# MainBoardSchematic.net
KiCad netlist of a schematic drawn in Altium Designer
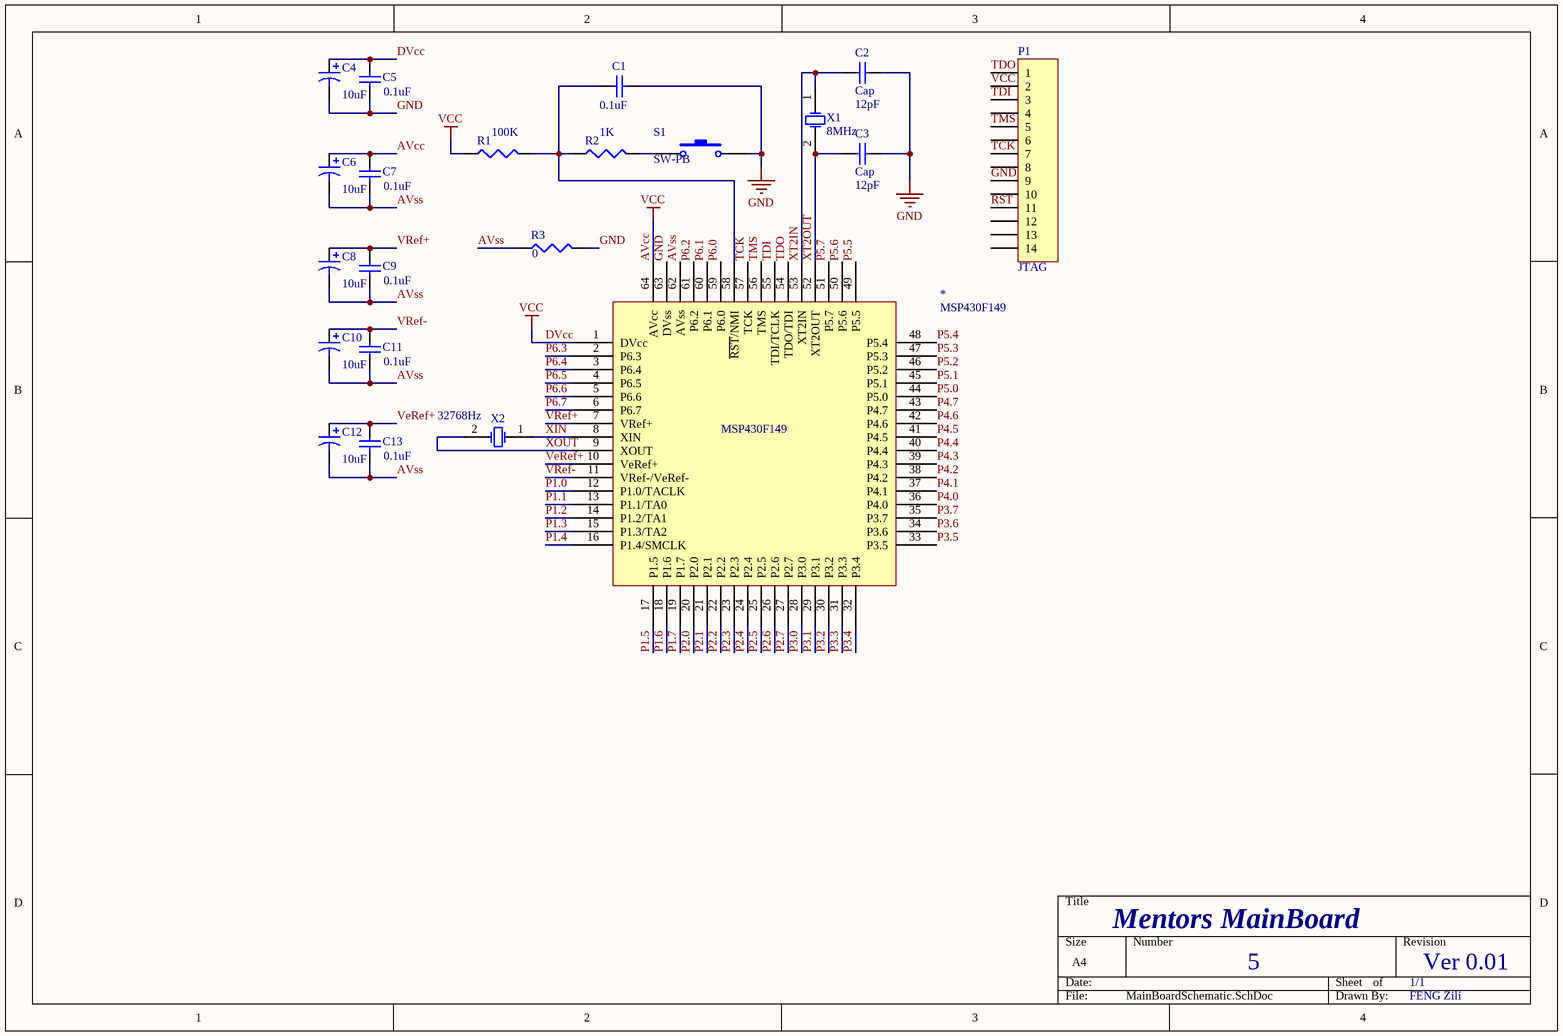
[diagram p0: MainBoardSchematic.SchDoc]

(export (version "E")
  (design (tool "Eeschema 10.0.6"))
  (components
    (comp (ref "*") (value "MSP430F149") (libsource (lib "schMSP430") (part "MSP430F149")))
    (comp (ref "C1")
      (value "0.1uF")
      (footprint "RAD-0.3")
      (description "Capacitor")
      (fields (field (name "Comment") "Cap") (field (name "PUBLISHER") "Altium Limited"))
      (libsource (lib "Miscellaneous Devices") (part "Cap"))
    )
    (comp (ref "C2")
      (value "Cap")
      (footprint "RAD-0.3")
      (description "Capacitor")
      (fields (field (name "ALTIUM_VALUE") "12pF") (field (name "PUBLISHER") "Altium Limited"))
      (libsource (lib "Miscellaneous Devices") (part "Cap"))
    )
    (comp (ref "C3")
      (value "Cap")
      (footprint "RAD-0.3")
      (description "Capacitor")
      (fields (field (name "ALTIUM_VALUE") "12pF") (field (name "PUBLISHER") "Altium Limited"))
      (libsource (lib "Miscellaneous Devices") (part "Cap"))
    )
    (comp (ref "C4")
      (value "10uF")
      (footprint "C0805")
      (description "Polarized Capacitor (Surface Mount)")
      (fields (field (name "Comment") "Cap Pol3") (field (name "PUBLISHER") "Altium Limited"))
      (libsource (lib "Miscellaneous Devices") (part "Cap Pol3"))
    )
    (comp (ref "C5")
      (value "0.1uF")
      (footprint "RAD-0.3")
      (description "Capacitor")
      (fields (field (name "Comment") "Cap") (field (name "PUBLISHER") "Altium Limited"))
      (libsource (lib "Miscellaneous Devices") (part "Cap"))
    )
    (comp (ref "C6")
      (value "10uF")
      (footprint "C0805")
      (description "Polarized Capacitor (Surface Mount)")
      (fields (field (name "Comment") "Cap Pol3") (field (name "PUBLISHER") "Altium Limited"))
      (libsource (lib "Miscellaneous Devices") (part "Cap Pol3"))
    )
    (comp (ref "C7")
      (value "0.1uF")
      (footprint "RAD-0.3")
      (description "Capacitor")
      (fields (field (name "Comment") "Cap") (field (name "PUBLISHER") "Altium Limited"))
      (libsource (lib "Miscellaneous Devices") (part "Cap"))
    )
    (comp (ref "C8")
      (value "10uF")
      (footprint "C0805")
      (description "Polarized Capacitor (Surface Mount)")
      (fields (field (name "Comment") "Cap Pol3") (field (name "PUBLISHER") "Altium Limited"))
      (libsource (lib "Miscellaneous Devices") (part "Cap Pol3"))
    )
    (comp (ref "C9")
      (value "0.1uF")
      (footprint "RAD-0.3")
      (description "Capacitor")
      (fields (field (name "Comment") "Cap") (field (name "PUBLISHER") "Altium Limited"))
      (libsource (lib "Miscellaneous Devices") (part "Cap"))
    )
    (comp (ref "C10")
      (value "10uF")
      (footprint "C0805")
      (description "Polarized Capacitor (Surface Mount)")
      (fields (field (name "Comment") "Cap Pol3") (field (name "PUBLISHER") "Altium Limited"))
      (libsource (lib "Miscellaneous Devices") (part "Cap Pol3"))
    )
    (comp (ref "C11")
      (value "0.1uF")
      (footprint "RAD-0.3")
      (description "Capacitor")
      (fields (field (name "Comment") "Cap") (field (name "PUBLISHER") "Altium Limited"))
      (libsource (lib "Miscellaneous Devices") (part "Cap"))
    )
    (comp (ref "C12")
      (value "10uF")
      (footprint "C0805")
      (description "Polarized Capacitor (Surface Mount)")
      (fields (field (name "Comment") "Cap Pol3") (field (name "PUBLISHER") "Altium Limited"))
      (libsource (lib "Miscellaneous Devices") (part "Cap Pol3"))
    )
    (comp (ref "C13")
      (value "0.1uF")
      (footprint "RAD-0.3")
      (description "Capacitor")
      (fields (field (name "Comment") "Cap") (field (name "PUBLISHER") "Altium Limited"))
      (libsource (lib "Miscellaneous Devices") (part "Cap"))
    )
    (comp (ref "P1")
      (value "JTAG")
      (footprint "HDR1X14")
      (description "Header, 14-Pin")
      (fields (field (name "PUBLISHER") "Altium Limited"))
      (libsource (lib "Miscellaneous Connectors") (part "Header 14"))
    )
    (comp (ref "R1")
      (value "100K")
      (footprint "J1-0603")
      (description "Resistor")
      (fields (field (name "Comment") "Res3") (field (name "PUBLISHER") "Altium Limited"))
      (libsource (lib "Miscellaneous Devices") (part "Res3"))
    )
    (comp (ref "R2")
      (value "1K")
      (footprint "J1-0603")
      (description "Resistor")
      (fields (field (name "PUBLISHER") "Altium Limited"))
      (libsource (lib "Miscellaneous Devices") (part "Res3"))
    )
    (comp (ref "R3")
      (value "0")
      (footprint "J1-0603")
      (description "Resistor")
      (fields (field (name "PUBLISHER") "Altium Limited"))
      (libsource (lib "Miscellaneous Devices") (part "Res3"))
    )
    (comp (ref "S1")
      (value "SW-PB")
      (footprint "SPST-2")
      (description "Switch")
      (fields (field (name "PUBLISHER") "Altium Limited"))
      (libsource (lib "Miscellaneous Devices") (part "SW-PB"))
    )
    (comp (ref "X1")
      (value "8MHz")
      (footprint "R38")
      (description "Crystal Oscillator")
      (fields (field (name "PUBLISHER") "Altium Limited"))
      (libsource (lib "Miscellaneous Devices") (part "XTAL"))
    )
    (comp (ref "X2")
      (value "32768Hz")
      (footprint "R38")
      (description "Crystal Oscillator")
      (fields (field (name "PUBLISHER") "Altium Limited"))
      (libsource (lib "Miscellaneous Devices") (part "XTAL"))
    )
  )
  (nets
    (net (code "1") (name "/AVss") (class "Default")
      (node (ref "*") (pin "62") (pinfunction "AVss_62") (pintype "passive"))
      (node (ref "C10") (pin "2") (pinfunction "2_2") (pintype "passive"))
      (node (ref "C11") (pin "1") (pinfunction "1_1") (pintype "passive"))
      (node (ref "C12") (pin "2") (pinfunction "2_2") (pintype "passive"))
      (node (ref "C13") (pin "1") (pinfunction "1_1") (pintype "passive"))
      (node (ref "C6") (pin "2") (pinfunction "2_2") (pintype "passive"))
      (node (ref "C7") (pin "1") (pinfunction "1_1") (pintype "passive"))
      (node (ref "C8") (pin "2") (pinfunction "2_2") (pintype "passive"))
      (node (ref "C9") (pin "1") (pinfunction "1_1") (pintype "passive"))
      (node (ref "R3") (pin "1") (pinfunction "1_1") (pintype "passive"))
    )
    (net (code "2") (name "/P1.0") (class "Default")
      (node (ref "*") (pin "12") (pinfunction "P1.0/TACLK_12") (pintype "passive"))
    )
    (net (code "3") (name "/P1.1") (class "Default")
      (node (ref "*") (pin "13") (pinfunction "P1.1/TA0_13") (pintype "passive"))
    )
    (net (code "4") (name "/P1.2") (class "Default")
      (node (ref "*") (pin "14") (pinfunction "P1.2/TA1_14") (pintype "passive"))
    )
    (net (code "5") (name "/P1.3") (class "Default")
      (node (ref "*") (pin "15") (pinfunction "P1.3/TA2_15") (pintype "passive"))
    )
    (net (code "6") (name "/P1.4") (class "Default")
      (node (ref "*") (pin "16") (pinfunction "P1.4/SMCLK_16") (pintype "passive"))
    )
    (net (code "7") (name "/P1.5") (class "Default")
      (node (ref "*") (pin "17") (pinfunction "P1.5_17") (pintype "passive"))
    )
    (net (code "8") (name "/P1.6") (class "Default")
      (node (ref "*") (pin "18") (pinfunction "P1.6_18") (pintype "passive"))
    )
    (net (code "9") (name "/P1.7") (class "Default")
      (node (ref "*") (pin "19") (pinfunction "P1.7_19") (pintype "passive"))
    )
    (net (code "10") (name "/P2.0") (class "Default")
      (node (ref "*") (pin "20") (pinfunction "P2.0_20") (pintype "passive"))
    )
    (net (code "11") (name "/P2.1") (class "Default")
      (node (ref "*") (pin "21") (pinfunction "P2.1_21") (pintype "passive"))
    )
    (net (code "12") (name "/P2.2") (class "Default")
      (node (ref "*") (pin "22") (pinfunction "P2.2_22") (pintype "passive"))
    )
    (net (code "13") (name "/P2.3") (class "Default")
      (node (ref "*") (pin "23") (pinfunction "P2.3_23") (pintype "passive"))
    )
    (net (code "14") (name "/P2.4") (class "Default")
      (node (ref "*") (pin "24") (pinfunction "P2.4_24") (pintype "passive"))
    )
    (net (code "15") (name "/P2.5") (class "Default")
      (node (ref "*") (pin "25") (pinfunction "P2.5_25") (pintype "passive"))
    )
    (net (code "16") (name "/P2.6") (class "Default")
      (node (ref "*") (pin "26") (pinfunction "P2.6_26") (pintype "passive"))
    )
    (net (code "17") (name "/P2.7") (class "Default")
      (node (ref "*") (pin "27") (pinfunction "P2.7_27") (pintype "passive"))
    )
    (net (code "18") (name "/P3.0") (class "Default")
      (node (ref "*") (pin "28") (pinfunction "P3.0_28") (pintype "passive"))
    )
    (net (code "19") (name "/P3.1") (class "Default")
      (node (ref "*") (pin "29") (pinfunction "P3.1_29") (pintype "passive"))
    )
    (net (code "20") (name "/P3.2") (class "Default")
      (node (ref "*") (pin "30") (pinfunction "P3.2_30") (pintype "passive"))
    )
    (net (code "21") (name "/P3.3") (class "Default")
      (node (ref "*") (pin "31") (pinfunction "P3.3_31") (pintype "passive"))
    )
    (net (code "22") (name "/P3.4") (class "Default")
      (node (ref "*") (pin "32") (pinfunction "P3.4_32") (pintype "passive"))
    )
    (net (code "23") (name "/P3.5") (class "Default")
      (node (ref "*") (pin "33") (pinfunction "P3.5_33") (pintype "passive"))
    )
    (net (code "24") (name "/P3.6") (class "Default")
      (node (ref "*") (pin "34") (pinfunction "P3.6_34") (pintype "passive"))
    )
    (net (code "25") (name "/P3.7") (class "Default")
      (node (ref "*") (pin "35") (pinfunction "P3.7_35") (pintype "passive"))
    )
    (net (code "26") (name "/P4.0") (class "Default")
      (node (ref "*") (pin "36") (pinfunction "P4.0_36") (pintype "passive"))
    )
    (net (code "27") (name "/P4.1") (class "Default")
      (node (ref "*") (pin "37") (pinfunction "P4.1_37") (pintype "passive"))
    )
    (net (code "28") (name "/P4.2") (class "Default")
      (node (ref "*") (pin "38") (pinfunction "P4.2_38") (pintype "passive"))
    )
    (net (code "29") (name "/P4.3") (class "Default")
      (node (ref "*") (pin "39") (pinfunction "P4.3_39") (pintype "passive"))
    )
    (net (code "30") (name "/P4.4") (class "Default")
      (node (ref "*") (pin "40") (pinfunction "P4.4_40") (pintype "passive"))
    )
    (net (code "31") (name "/P4.5") (class "Default")
      (node (ref "*") (pin "41") (pinfunction "P4.5_41") (pintype "passive"))
    )
    (net (code "32") (name "/P4.6") (class "Default")
      (node (ref "*") (pin "42") (pinfunction "P4.6_42") (pintype "passive"))
    )
    (net (code "33") (name "/P4.7") (class "Default")
      (node (ref "*") (pin "43") (pinfunction "P4.7_43") (pintype "passive"))
    )
    (net (code "34") (name "/P5.0") (class "Default")
      (node (ref "*") (pin "44") (pinfunction "P5.0_44") (pintype "passive"))
    )
    (net (code "35") (name "/P5.1") (class "Default")
      (node (ref "*") (pin "45") (pinfunction "P5.1_45") (pintype "passive"))
    )
    (net (code "36") (name "/P5.2") (class "Default")
      (node (ref "*") (pin "46") (pinfunction "P5.2_46") (pintype "passive"))
    )
    (net (code "37") (name "/P5.3") (class "Default")
      (node (ref "*") (pin "47") (pinfunction "P5.3_47") (pintype "passive"))
    )
    (net (code "38") (name "/P5.4") (class "Default")
      (node (ref "*") (pin "48") (pinfunction "P5.4_48") (pintype "passive"))
    )
    (net (code "39") (name "/P5.5") (class "Default")
      (node (ref "*") (pin "49") (pinfunction "P5.5_49") (pintype "passive"))
    )
    (net (code "40") (name "/P5.6") (class "Default")
      (node (ref "*") (pin "50") (pinfunction "P5.6_50") (pintype "passive"))
    )
    (net (code "41") (name "/P5.7") (class "Default")
      (node (ref "*") (pin "51") (pinfunction "P5.7_51") (pintype "passive"))
    )
    (net (code "42") (name "/P6.0") (class "Default")
      (node (ref "*") (pin "59") (pinfunction "P6.0_59") (pintype "passive"))
    )
    (net (code "43") (name "/P6.1") (class "Default")
      (node (ref "*") (pin "60") (pinfunction "P6.1_60") (pintype "passive"))
    )
    (net (code "44") (name "/P6.2") (class "Default")
      (node (ref "*") (pin "61") (pinfunction "P6.2_61") (pintype "passive"))
    )
    (net (code "45") (name "/P6.3") (class "Default")
      (node (ref "*") (pin "2") (pinfunction "P6.3_2") (pintype "passive"))
    )
    (net (code "46") (name "/P6.4") (class "Default")
      (node (ref "*") (pin "3") (pinfunction "P6.4_3") (pintype "passive"))
    )
    (net (code "47") (name "/P6.5") (class "Default")
      (node (ref "*") (pin "4") (pinfunction "P6.5_4") (pintype "passive"))
    )
    (net (code "48") (name "/P6.6") (class "Default")
      (node (ref "*") (pin "5") (pinfunction "P6.6_5") (pintype "passive"))
    )
    (net (code "49") (name "/P6.7") (class "Default")
      (node (ref "*") (pin "6") (pinfunction "P6.7_6") (pintype "passive"))
    )
    (net (code "50") (name "/RST") (class "Default")
      (node (ref "P1") (pin "11") (pinfunction "11_11") (pintype "passive"))
    )
    (net (code "51") (name "/TCK") (class "Default")
      (node (ref "*") (pin "57") (pinfunction "TCK_57") (pintype "passive"))
      (node (ref "P1") (pin "7") (pinfunction "7_7") (pintype "passive"))
    )
    (net (code "52") (name "/TDI") (class "Default")
      (node (ref "*") (pin "55") (pinfunction "TDI/TCLK_55") (pintype "passive"))
      (node (ref "P1") (pin "3") (pinfunction "3_3") (pintype "passive"))
    )
    (net (code "53") (name "/TDO") (class "Default")
      (node (ref "*") (pin "54") (pinfunction "TDO/TDI_54") (pintype "passive"))
      (node (ref "P1") (pin "1") (pinfunction "1_1") (pintype "passive"))
    )
    (net (code "54") (name "/TMS") (class "Default")
      (node (ref "*") (pin "56") (pinfunction "TMS_56") (pintype "passive"))
      (node (ref "P1") (pin "5") (pinfunction "5_5") (pintype "passive"))
    )
    (net (code "55") (name "/VRef+") (class "Default")
      (node (ref "*") (pin "7") (pinfunction "VRef+_7") (pintype "passive"))
      (node (ref "C8") (pin "1") (pinfunction "1_1") (pintype "passive"))
      (node (ref "C9") (pin "2") (pinfunction "2_2") (pintype "passive"))
    )
    (net (code "56") (name "/VRef-") (class "Default")
      (node (ref "*") (pin "11") (pinfunction "VRef-/VeRef-_11") (pintype "passive"))
      (node (ref "C10") (pin "1") (pinfunction "1_1") (pintype "passive"))
      (node (ref "C11") (pin "2") (pinfunction "2_2") (pintype "passive"))
    )
    (net (code "57") (name "/VeRef+") (class "Default")
      (node (ref "*") (pin "10") (pinfunction "VeRef+_10") (pintype "passive"))
      (node (ref "C12") (pin "1") (pinfunction "1_1") (pintype "passive"))
      (node (ref "C13") (pin "2") (pinfunction "2_2") (pintype "passive"))
    )
    (net (code "58") (name "/XIN") (class "Default")
      (node (ref "*") (pin "8") (pinfunction "XIN_8") (pintype "passive"))
      (node (ref "X2") (pin "1") (pinfunction "OSC1_1") (pintype "passive"))
    )
    (net (code "59") (name "/XOUT") (class "Default")
      (node (ref "*") (pin "9") (pinfunction "XOUT_9") (pintype "passive"))
      (node (ref "X2") (pin "2") (pinfunction "OSC2_2") (pintype "passive"))
    )
    (net (code "60") (name "/XT2IN") (class "Default")
      (node (ref "*") (pin "53") (pinfunction "XT2IN_53") (pintype "passive"))
      (node (ref "C2") (pin "2") (pinfunction "2_2") (pintype "passive"))
      (node (ref "X1") (pin "1") (pinfunction "OSC1_1") (pintype "passive"))
    )
    (net (code "61") (name "/XT2OUT") (class "Default")
      (node (ref "*") (pin "52") (pinfunction "XT2OUT_52") (pintype "passive"))
      (node (ref "C3") (pin "2") (pinfunction "2_2") (pintype "passive"))
      (node (ref "X1") (pin "2") (pinfunction "OSC2_2") (pintype "passive"))
    )
    (net (code "62") (name "GND") (class "Default")
      (node (ref "*") (pin "63") (pinfunction "DVss_63") (pintype "passive"))
      (node (ref "C1") (pin "2") (pinfunction "2_2") (pintype "passive"))
      (node (ref "C2") (pin "1") (pinfunction "1_1") (pintype "passive"))
      (node (ref "C3") (pin "1") (pinfunction "1_1") (pintype "passive"))
      (node (ref "C4") (pin "2") (pinfunction "2_2") (pintype "passive"))
      (node (ref "C5") (pin "1") (pinfunction "1_1") (pintype "passive"))
      (node (ref "P1") (pin "9") (pinfunction "9_9") (pintype "passive"))
      (node (ref "R3") (pin "2") (pinfunction "2_2") (pintype "passive"))
      (node (ref "S1") (pin "2") (pinfunction "2_2") (pintype "passive"))
    )
    (net (code "63") (name "Net-(*-~{RST}{slash}NMI)") (class "Default")
      (node (ref "*") (pin "58") (pinfunction "~{RST}/NMI_58") (pintype "passive"))
      (node (ref "C1") (pin "1") (pinfunction "1_1") (pintype "passive"))
      (node (ref "R1") (pin "2") (pinfunction "2_2") (pintype "passive"))
      (node (ref "R2") (pin "1") (pinfunction "1_1") (pintype "passive"))
    )
    (net (code "64") (name "Net-(R2-Pad2)") (class "Default")
      (node (ref "R2") (pin "2") (pinfunction "2_2") (pintype "passive"))
      (node (ref "S1") (pin "1") (pinfunction "1_1") (pintype "passive"))
    )
    (net (code "65") (name "VCC") (class "Default")
      (node (ref "*") (pin "1") (pinfunction "DVcc_1") (pintype "passive"))
      (node (ref "*") (pin "64") (pinfunction "AVcc_64") (pintype "passive"))
      (node (ref "C4") (pin "1") (pinfunction "1_1") (pintype "passive"))
      (node (ref "C5") (pin "2") (pinfunction "2_2") (pintype "passive"))
      (node (ref "C6") (pin "1") (pinfunction "1_1") (pintype "passive"))
      (node (ref "C7") (pin "2") (pinfunction "2_2") (pintype "passive"))
      (node (ref "P1") (pin "2") (pinfunction "2_2") (pintype "passive"))
      (node (ref "R1") (pin "1") (pinfunction "1_1") (pintype "passive"))
    )
    (net (code "66") (name "unconnected-(P1-Pad4)") (class "Default")
      (node (ref "P1") (pin "4") (pinfunction "4_4") (pintype "passive"))
    )
    (net (code "67") (name "unconnected-(P1-Pad6)") (class "Default")
      (node (ref "P1") (pin "6") (pinfunction "6_6") (pintype "passive"))
    )
    (net (code "68") (name "unconnected-(P1-Pad8)") (class "Default")
      (node (ref "P1") (pin "8") (pinfunction "8_8") (pintype "passive"))
    )
    (net (code "69") (name "unconnected-(P1-Pad10)") (class "Default")
      (node (ref "P1") (pin "10") (pinfunction "10_10") (pintype "passive"))
    )
    (net (code "70") (name "unconnected-(P1-Pad12)") (class "Default")
      (node (ref "P1") (pin "12") (pinfunction "12_12") (pintype "passive"))
    )
    (net (code "71") (name "unconnected-(P1-Pad13)") (class "Default")
      (node (ref "P1") (pin "13") (pinfunction "13_13") (pintype "passive"))
    )
    (net (code "72") (name "unconnected-(P1-Pad14)") (class "Default")
      (node (ref "P1") (pin "14") (pinfunction "14_14") (pintype "passive"))
    )
  )
)
